# IdealDiode.net
KiCad netlist of a schematic drawn in Altium Designer
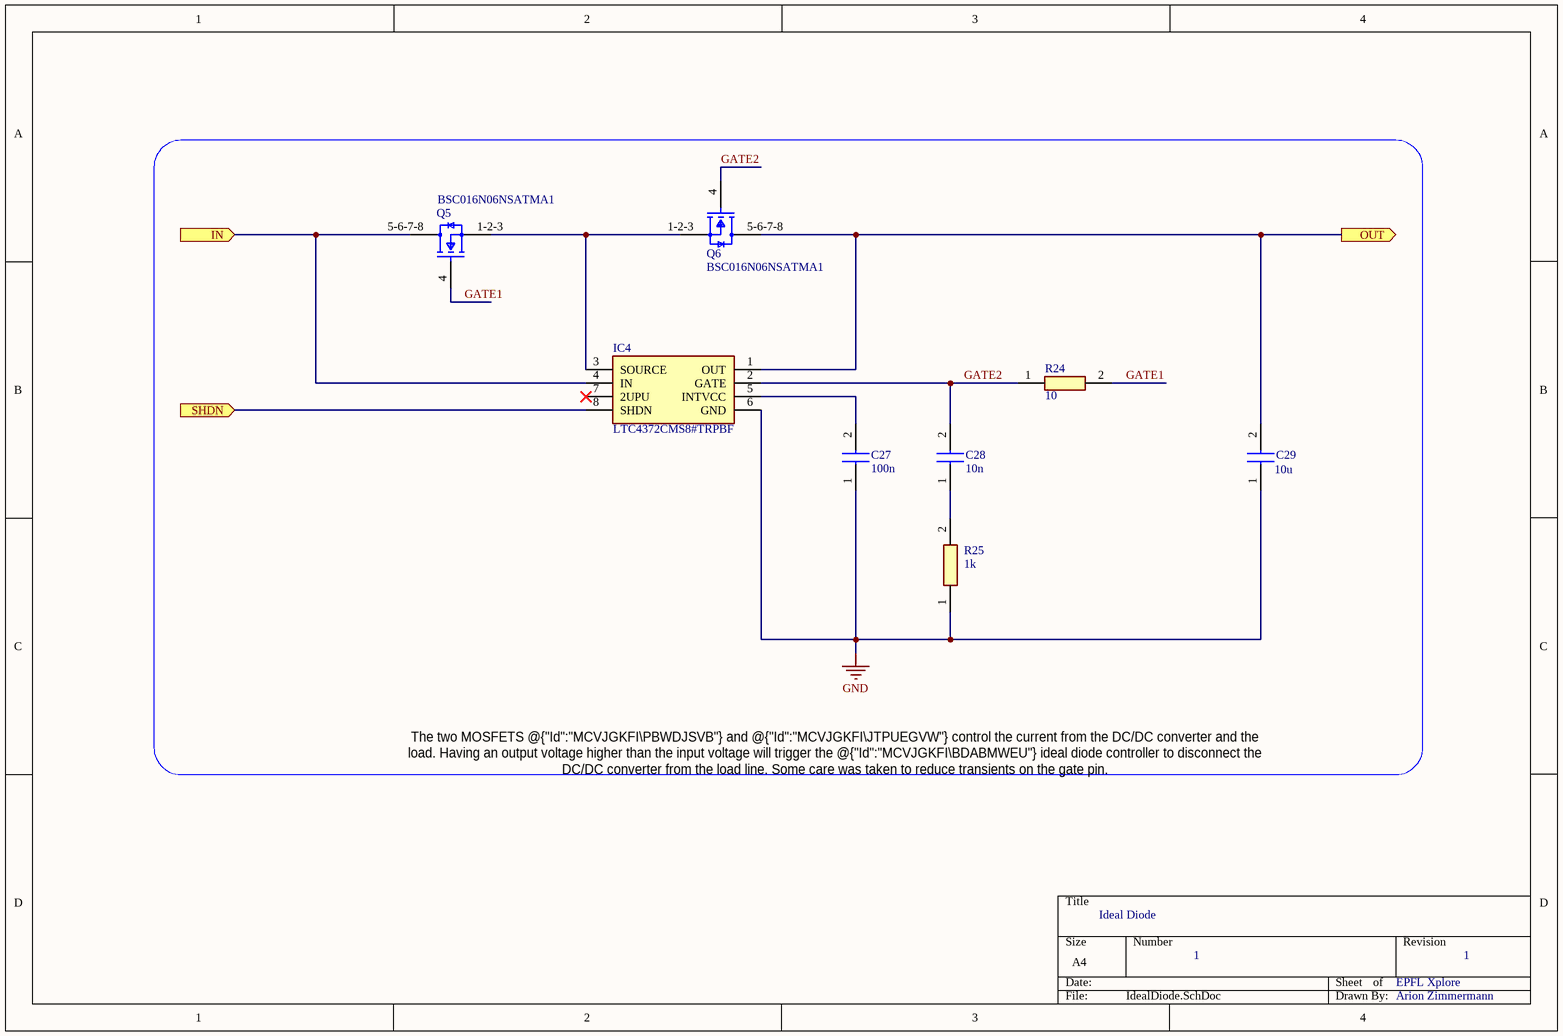
[diagram p0: IdealDiode.SchDoc]

(export (version "E")
  (design (tool "Eeschema 10.0.6"))
  (components
    (comp (ref "C27")
      (value "100n")
      (footprint "CAPC1608X95N")
      (description "Capacitor")
      (fields
        (field (name "MANUFACTURER_PART_NUMBER") "C0603C104K5RACTU")
        (field (name "MOUSER PART NUMBER") "80-C0603C104K5R")
      )
      (libsource (lib "*") (part "C0603C104K5RACTU"))
    )
    (comp (ref "C28")
      (value "10n")
      (footprint "CAPC1608X95N")
      (description "Capacitor")
      (fields
        (field (name "MANUFACTURER_PART_NUMBER") "C0603C104K5RACTU")
        (field (name "MOUSER PART NUMBER") "80-C0603C104K5R")
      )
      (libsource (lib "*") (part "C0603C104K5RACTU"))
    )
    (comp (ref "C29")
      (value "10u")
      (footprint "CAPC3225X230N")
      (description "Capacitor")
      (fields
        (field (name "MANUFACTURER_PART_NUMBER") "C3225X7R2A106K250AC")
        (field (name "MOUSER PART NUMBER") "810-C3225X7R2A106K25")
      )
      (libsource (lib "SamacSys") (part "C3225X7R2A106K250AC"))
    )
    (comp (ref "IC4")
      (value "LTC4372CMS8#TRPBF")
      (footprint "SOP65P490X110-8N")
      (description "Integrated Circuit")
      (fields (field (name "MOUSER PART NUMBER") "584-LTC4372CMS8TRPBF"))
      (libsource (lib "*") (part "LTC4372CMS8#TRPBF"))
    )
    (comp (ref "Q5")
      (value "BSC016N06NSATMA1")
      (footprint "FP-PG-TDSON-8-MFG")
      (description "MOSFET N-CH 60V 30A TDSON-8")
      (fields
        (field (name "OCTOPART") "https://octopart.com/bsc016n06nsatma1-infineon-23421881")
        (field (name "MANUFACTURER") "Infineon")
      )
      (libsource (lib "Altium Content Vault") (part "1b0cff3a23bd3632373e77d40b07099"))
    )
    (comp (ref "Q6")
      (value "BSC016N06NSATMA1")
      (footprint "FP-PG-TDSON-8-MFG")
      (description "MOSFET N-CH 60V 30A TDSON-8")
      (fields
        (field (name "OCTOPART") "https://octopart.com/bsc016n06nsatma1-infineon-23421881")
        (field (name "MANUFACTURER") "Infineon")
      )
      (libsource (lib "Altium Content Vault") (part "1b0cff3a23bd3632373e77d40b07099"))
    )
    (comp (ref "R24")
      (value "10")
      (footprint "RESC1608X55N")
      (description "Resistor")
      (fields
        (field (name "MANUFACTURER_PART_NUMBER") "CRCW0603100RFKEBC")
        (field (name "MOUSER PART NUMBER") "71-CRCW0603100RFKEBC")
      )
      (libsource (lib "") (part "CRCW0603100RFKEBC_1"))
    )
    (comp (ref "R25")
      (value "1k")
      (footprint "RESC1608X55N")
      (description "Resistor")
      (fields
        (field (name "MANUFACTURER_PART_NUMBER") "CRCW0603100RFKEBC")
        (field (name "MOUSER PART NUMBER") "71-CRCW0603100RFKEBC")
      )
      (libsource (lib "*") (part "CRCW0603100RFKEBC"))
    )
  )
  (nets
    (net (code "1") (name "/GATE1") (class "Default")
      (node (ref "Q5") (pin "4") (pinfunction "G_4") (pintype "passive"))
      (node (ref "R24") (pin "2") (pinfunction "2_2") (pintype "passive"))
    )
    (net (code "2") (name "/GATE2") (class "Default")
      (node (ref "C28") (pin "2") (pinfunction "2_2") (pintype "passive"))
      (node (ref "IC4") (pin "2") (pinfunction "GATE_2") (pintype "passive"))
      (node (ref "Q6") (pin "4") (pinfunction "G_4") (pintype "passive"))
      (node (ref "R24") (pin "1") (pinfunction "1_1") (pintype "passive"))
    )
    (net (code "3") (name "/IN") (class "Default")
      (node (ref "IC4") (pin "4") (pinfunction "IN_4") (pintype "passive"))
      (node (ref "Q5") (pin "5-6-7-8") (pinfunction "D_5-6-7-8") (pintype "passive"))
    )
    (net (code "4") (name "/OUT") (class "Default")
      (node (ref "C29") (pin "2") (pinfunction "2_2") (pintype "passive"))
      (node (ref "IC4") (pin "1") (pinfunction "OUT_1") (pintype "passive"))
      (node (ref "Q6") (pin "5-6-7-8") (pinfunction "D_5-6-7-8") (pintype "passive"))
    )
    (net (code "5") (name "/SHDN") (class "Default")
      (node (ref "IC4") (pin "8") (pinfunction "SHDN_8") (pintype "passive"))
    )
    (net (code "6") (name "GND") (class "Default")
      (node (ref "C27") (pin "1") (pinfunction "1_1") (pintype "passive"))
      (node (ref "C29") (pin "1") (pinfunction "1_1") (pintype "passive"))
      (node (ref "IC4") (pin "6") (pinfunction "GND_6") (pintype "passive"))
      (node (ref "R25") (pin "1") (pinfunction "1_1") (pintype "passive"))
    )
    (net (code "7") (name "Net-(C28-Pad1)") (class "Default")
      (node (ref "C28") (pin "1") (pinfunction "1_1") (pintype "passive"))
      (node (ref "R25") (pin "2") (pinfunction "2_2") (pintype "passive"))
    )
    (net (code "8") (name "Net-(IC4-INTVCC)") (class "Default")
      (node (ref "C27") (pin "2") (pinfunction "2_2") (pintype "passive"))
      (node (ref "IC4") (pin "5") (pinfunction "INTVCC_5") (pintype "passive"))
    )
    (net (code "9") (name "Net-(IC4-SOURCE)") (class "Default")
      (node (ref "IC4") (pin "3") (pinfunction "SOURCE_3") (pintype "passive"))
      (node (ref "Q5") (pin "1-2-3") (pinfunction "S_1-2-3") (pintype "passive"))
      (node (ref "Q6") (pin "1-2-3") (pinfunction "S_1-2-3") (pintype "passive"))
    )
    (net (code "10") (name "unconnected-(IC4-2UPU-Pad7)") (class "Default")
      (node (ref "IC4") (pin "7") (pinfunction "2UPU_7") (pintype "passive+no_connect"))
    )
  )
)
